# fans.net
KiCad netlist of a schematic drawn in Altium Designer
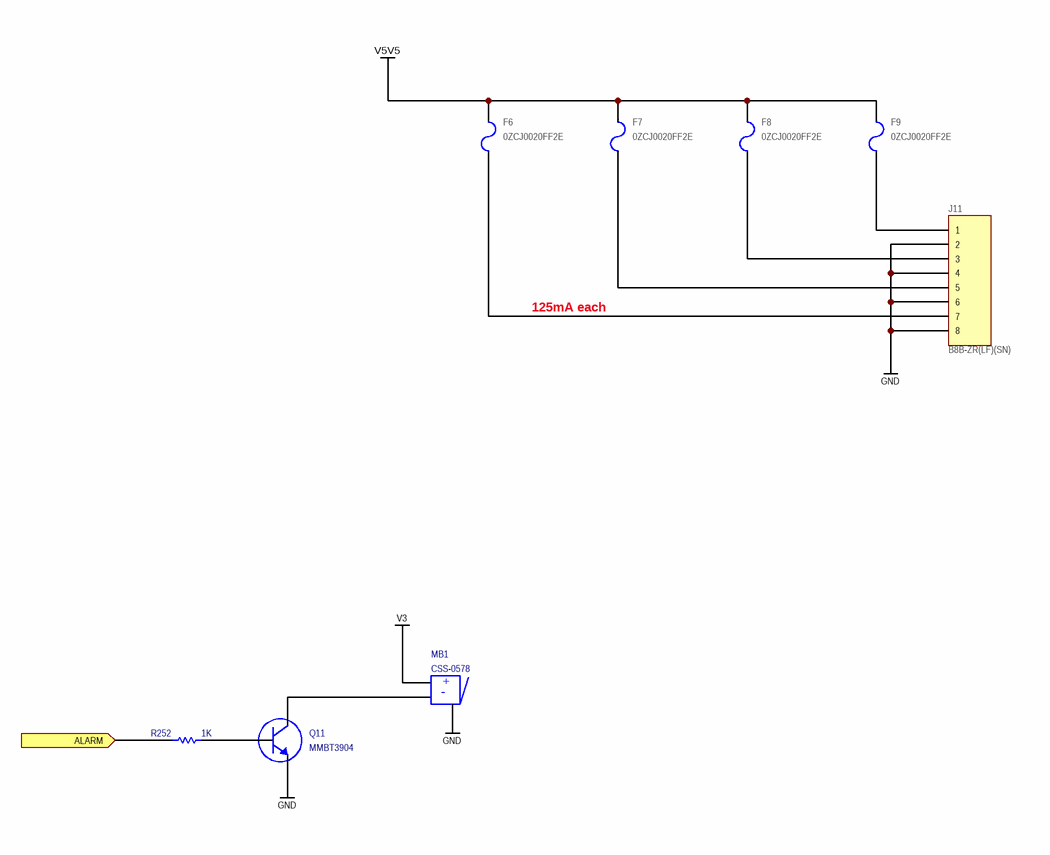
[diagram p0: fans.SchDoc]

(export (version "E")
  (design (tool "Eeschema 10.0.6"))
  (components
    (comp (ref "F6")
      (value "0ZCJ0020FF2E")
      (footprint "generic:1206")
      (description "PTC Resettable Fuse, 0.2A, 30V, SMD 1206")
      (fields (field (name "MANUFACTURER") "Bell Fuse"))
      (libsource (lib "bel-fuse") (part "0ZCJ0020FF2E"))
    )
    (comp (ref "F7")
      (value "0ZCJ0020FF2E")
      (footprint "generic:1206")
      (description "PTC Resettable Fuse, 0.2A, 30V, SMD 1206")
      (fields (field (name "MANUFACTURER") "Bell Fuse"))
      (libsource (lib "bel-fuse") (part "0ZCJ0020FF2E"))
    )
    (comp (ref "F8")
      (value "0ZCJ0020FF2E")
      (footprint "generic:1206")
      (description "PTC Resettable Fuse, 0.2A, 30V, SMD 1206")
      (fields (field (name "MANUFACTURER") "Bell Fuse"))
      (libsource (lib "bel-fuse") (part "0ZCJ0020FF2E"))
    )
    (comp (ref "F9")
      (value "0ZCJ0020FF2E")
      (footprint "generic:1206")
      (description "PTC Resettable Fuse, 0.2A, 30V, SMD 1206")
      (fields (field (name "MANUFACTURER") "Bell Fuse"))
      (libsource (lib "bel-fuse") (part "0ZCJ0020FF2E"))
    )
    (comp (ref "J11")
      (value "B8B-ZR(LF)(SN)")
      (footprint "jst:B8B-ZR")
      (description "Through-hole Shrouded Header 8-Position")
      (fields (field (name "MANUFACTURER") "JST"))
      (libsource (lib "Miscellaneous Connectors") (part "Header 8"))
    )
    (comp (ref "MB1")
      (value "CSS-0578")
      (footprint "CSS-0578")
      (description "Magnetic Buzzer")
      (fields (field (name "MANUFACTURER") "CUI, Inc."))
      (libsource (lib "generic") (part "CSS-0578"))
    )
    (comp (ref "Q11")
      (value "MMBT3904")
      (footprint "SOT23")
      (description "NPN General Purpose Amplifier")
      (fields (field (name "MANUFACTURER") "Fairchild Semiconductor"))
      (libsource (lib "fairchild") (part "2N3904"))
    )
    (comp (ref "R252")
      (value "1K")
      (footprint "RESC1005X40N")
      (description "Thick Film Resistor 1k ±1% 0402")
      (fields (field (name "MANUFACTURER") "Yageo") (field (name "TOLERANCE") "±1%"))
      (libsource (lib "Graviton") (part "RES 0402"))
    )
  )
  (nets
    (net (code "1") (name "/ALARM") (class "Default")
      (node (ref "R252") (pin "2") (pinfunction "2_2") (pintype "passive"))
    )
    (net (code "2") (name "GND") (class "Default")
      (node (ref "J11") (pin "2") (pinfunction "2_2") (pintype "passive"))
      (node (ref "J11") (pin "4") (pinfunction "4_4") (pintype "passive"))
      (node (ref "J11") (pin "6") (pinfunction "6_6") (pintype "passive"))
      (node (ref "J11") (pin "8") (pinfunction "8_8") (pintype "passive"))
      (node (ref "MB1") (pin "3") (pinfunction "TAB_3") (pintype "passive"))
      (node (ref "Q11") (pin "2") (pinfunction "E_2") (pintype "passive"))
    )
    (net (code "3") (name "Net-(F6-Pad2)") (class "Default")
      (node (ref "F6") (pin "2") (pinfunction "2_2") (pintype "passive"))
      (node (ref "J11") (pin "7") (pinfunction "7_7") (pintype "passive"))
    )
    (net (code "4") (name "Net-(F7-Pad2)") (class "Default")
      (node (ref "F7") (pin "2") (pinfunction "2_2") (pintype "passive"))
      (node (ref "J11") (pin "5") (pinfunction "5_5") (pintype "passive"))
    )
    (net (code "5") (name "Net-(F8-Pad2)") (class "Default")
      (node (ref "F8") (pin "2") (pinfunction "2_2") (pintype "passive"))
      (node (ref "J11") (pin "3") (pinfunction "3_3") (pintype "passive"))
    )
    (net (code "6") (name "Net-(F9-Pad2)") (class "Default")
      (node (ref "F9") (pin "2") (pinfunction "2_2") (pintype "passive"))
      (node (ref "J11") (pin "1") (pinfunction "1_1") (pintype "passive"))
    )
    (net (code "7") (name "Net-(MB1-NEG)") (class "Default")
      (node (ref "MB1") (pin "2") (pinfunction "NEG_2") (pintype "passive"))
      (node (ref "Q11") (pin "3") (pinfunction "C_3") (pintype "passive"))
    )
    (net (code "8") (name "Net-(Q11-B)") (class "Default")
      (node (ref "Q11") (pin "1") (pinfunction "B_1") (pintype "passive"))
      (node (ref "R252") (pin "1") (pinfunction "1_1") (pintype "passive"))
    )
    (net (code "9") (name "V3") (class "Default")
      (node (ref "MB1") (pin "1") (pinfunction "POS_1") (pintype "passive"))
    )
    (net (code "10") (name "V5V5") (class "Default")
      (node (ref "F6") (pin "1") (pinfunction "1_1") (pintype "passive"))
      (node (ref "F7") (pin "1") (pinfunction "1_1") (pintype "passive"))
      (node (ref "F8") (pin "1") (pinfunction "1_1") (pintype "passive"))
      (node (ref "F9") (pin "1") (pinfunction "1_1") (pintype "passive"))
    )
  )
)
